# RTD_100R_INA_Comp.net
KiCad netlist of a schematic drawn in Altium Designer
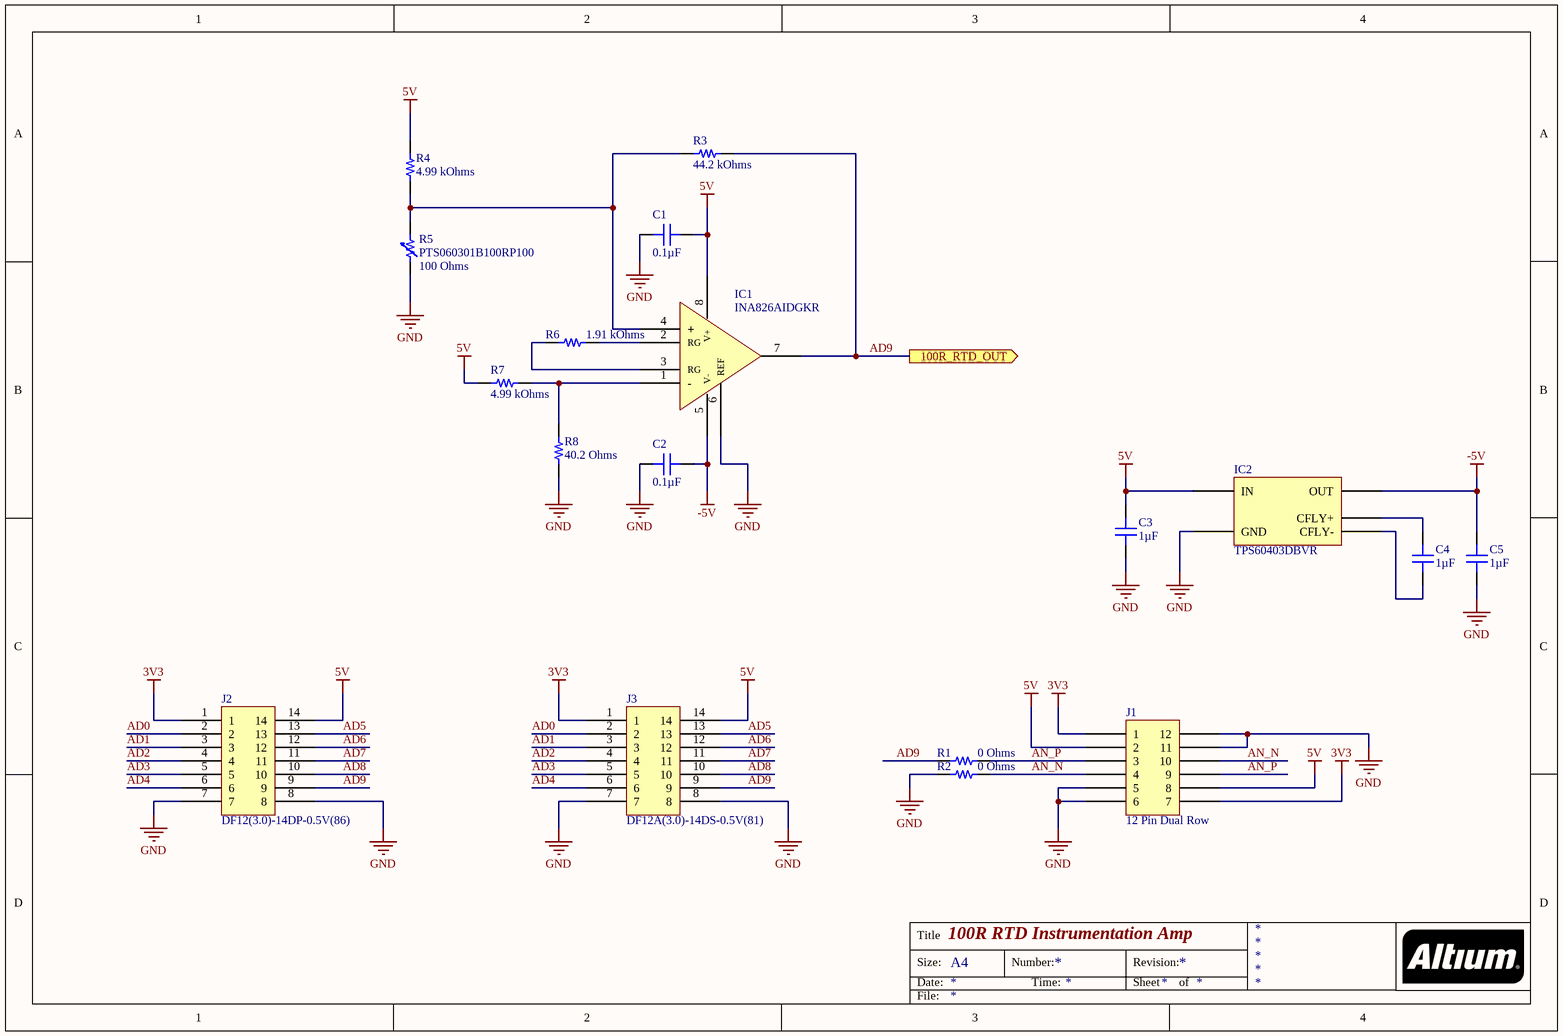
[diagram p0: RTD 100R INA Comp.SchDoc]

(export (version "E")
  (design (tool "Eeschema 10.0.6"))
  (components
    (comp (ref "C1")
      (value "0.1µF")
      (footprint "CAP 0603_1608")
      (description "CAP CER 0.1UF 16V Y5V 0603")
      (fields (field (name "PART NUMBER") "CC0603ZRY5V7BB104") (field (name "MANUFACTURER") "Yageo"))
      (libsource (lib "altiumlibrary.com") (part "Capacitor"))
    )
    (comp (ref "C2")
      (value "0.1µF")
      (footprint "CAP 0603_1608")
      (description "CAP CER 0.1UF 16V Y5V 0603")
      (fields (field (name "PART NUMBER") "CC0603ZRY5V7BB104") (field (name "MANUFACTURER") "Yageo"))
      (libsource (lib "altiumlibrary.com") (part "Capacitor"))
    )
    (comp (ref "C3")
      (value "1µF")
      (footprint "CAP 0603_1608")
      (description "CAP CER 1UF 25V X7R 0603")
      (fields
        (field (name "PART NUMBER") "CL10B105KA8NNNC")
        (field (name "MANUFACTURER") "Samsung Electro-Mechanics")
      )
      (libsource (lib "altiumlibrary.com") (part "Capacitor"))
    )
    (comp (ref "C4")
      (value "1µF")
      (footprint "CAP 0603_1608")
      (description "CAP CER 1UF 25V X7R 0603")
      (fields
        (field (name "PART NUMBER") "CL10B105KA8NNNC")
        (field (name "MANUFACTURER") "Samsung Electro-Mechanics")
      )
      (libsource (lib "altiumlibrary.com") (part "Capacitor"))
    )
    (comp (ref "C5")
      (value "1µF")
      (footprint "CAP 0603_1608")
      (description "CAP CER 1UF 25V X7R 0603")
      (fields
        (field (name "PART NUMBER") "CL10B105KA8NNNC")
        (field (name "MANUFACTURER") "Samsung Electro-Mechanics")
      )
      (libsource (lib "altiumlibrary.com") (part "Capacitor"))
    )
    (comp (ref "IC1")
      (value "INA826AIDGKR")
      (footprint "TI VSSOP-8 DGK")
      (description "IC INST AMP 1 CIRCUIT 8VSSOP")
      (fields (field (name "MANUFACTURER") "Texas Instruments"))
      (libsource (lib "altiumlibrary.com") (part "TI INA826"))
    )
    (comp (ref "IC2")
      (value "TPS60403DBVR")
      (footprint "TI SOT-23-5 DBV")
      (description "IC REG CHARG PUMP INV 60MA SOT23")
      (fields (field (name "MANUFACTURER") "Texas Instruments"))
      (libsource (lib "altiumlibrary.com") (part "TI TPS60403"))
    )
    (comp (ref "J1")
      (value "12 Pin Dual Row")
      (footprint "TE 5650118-3 Card Edge")
      (libsource (lib "CelestialUseful") (part "12 Pin Dual Row"))
    )
    (comp (ref "J2")
      (value "DF12(3.0)-14DP-0.5V(86)")
      (footprint "HIROSE DF12 3.0-14DP-0.5V 86")
      (description "CONN HDR 14POS SMD GOLD")
      (fields (field (name "MANUFACTURER") "Hirose Electric Co Ltd"))
      (libsource (lib "altiumlibrary.com") (part "14 Pin Dual Row"))
    )
    (comp (ref "J3")
      (value "DF12A(3.0)-14DS-0.5V(81)")
      (footprint "HIROSE DF12A 3.0-14DS-0.5V 81")
      (description "CONN RCPT 14POS SMD GOLD")
      (fields (field (name "MANUFACTURER") "Hirose Electric Co Ltd"))
      (libsource (lib "altiumlibrary.com") (part "14 Pin Dual Row"))
    )
    (comp (ref "R1")
      (value "0 Ohms")
      (footprint "RES 0603_1608")
      (description "RES SMD 0 OHM JUMPER 1/10W 0603")
      (fields
        (field (name "PART NUMBER") "ERJ-3GEY0R00V")
        (field (name "MANUFACTURER") "Panasonic Electronic Components")
      )
      (libsource (lib "altiumlibrary.com") (part "Resistor"))
    )
    (comp (ref "R2")
      (value "0 Ohms")
      (footprint "RES 0603_1608")
      (description "RES SMD 0 OHM JUMPER 1/10W 0603")
      (fields
        (field (name "PART NUMBER") "ERJ-3GEY0R00V")
        (field (name "MANUFACTURER") "Panasonic Electronic Components")
      )
      (libsource (lib "altiumlibrary.com") (part "Resistor"))
    )
    (comp (ref "R3")
      (value "44.2 kOhms")
      (footprint "RES 0603_1608")
      (description "RES SMD 44.2K OHM 1% 1/10W 0603")
      (fields
        (field (name "PART NUMBER") "ERJ-3EKF4422V")
        (field (name "MANUFACTURER") "Panasonic Electronic Components")
      )
      (libsource (lib "altiumlibrary.com") (part "Resistor"))
    )
    (comp (ref "R4")
      (value "4.99 kOhms")
      (footprint "RES 0603_1608")
      (description "RES SMD 4.99K OHM 1% 1/10W 0603")
      (fields
        (field (name "PART NUMBER") "ERJ-3EKF4991V")
        (field (name "MANUFACTURER") "Panasonic Electronic Components")
      )
      (libsource (lib "altiumlibrary.com") (part "Resistor"))
    )
    (comp (ref "R5")
      (value "PTS060301B100RP100")
      (footprint "RTD 0603_1608")
      (description "SENSOR RTD 100OHM 1% 0603")
      (fields (field (name "MANUFACTURER") "Vishay Beyschlag") (field (name "RESISTANCE @ 0°C") "100 Ohms"))
      (libsource (lib "altiumlibrary.com") (part "RTD"))
    )
    (comp (ref "R6")
      (value "1.91 kOhms")
      (footprint "RES 0603_1608")
      (description "RES SMD 1.91K OHM 1% 1/10W 0603")
      (fields
        (field (name "PART NUMBER") "ERJ-3EKF1911V")
        (field (name "MANUFACTURER") "Panasonic Electronic Components")
      )
      (libsource (lib "altiumlibrary.com") (part "Resistor"))
    )
    (comp (ref "R7")
      (value "4.99 kOhms")
      (footprint "RES 0603_1608")
      (description "RES SMD 4.99K OHM 1% 1/10W 0603")
      (fields
        (field (name "PART NUMBER") "ERJ-3EKF4991V")
        (field (name "MANUFACTURER") "Panasonic Electronic Components")
      )
      (libsource (lib "altiumlibrary.com") (part "Resistor"))
    )
    (comp (ref "R8")
      (value "40.2 Ohms")
      (footprint "RES 0603_1608")
      (description "RES SMD 40.2 OHM 1% 1/10W 0603")
      (fields
        (field (name "PART NUMBER") "ERJ-3EKF40R2V")
        (field (name "MANUFACTURER") "Panasonic Electronic Components")
      )
      (libsource (lib "altiumlibrary.com") (part "Resistor"))
    )
  )
  (nets
    (net (code "1") (name "-5V") (class "Default")
      (node (ref "C2") (pin "2") (pinfunction "2_2") (pintype "passive"))
      (node (ref "C5") (pin "2") (pinfunction "2_2") (pintype "passive"))
      (node (ref "IC1") (pin "5") (pinfunction "V-_5") (pintype "passive"))
      (node (ref "IC2") (pin "1") (pinfunction "OUT_1") (pintype "passive"))
    )
    (net (code "2") (name "/AD0") (class "Default")
      (node (ref "J2") (pin "2") (pinfunction "2_2") (pintype "passive"))
      (node (ref "J3") (pin "2") (pinfunction "2_2") (pintype "passive"))
    )
    (net (code "3") (name "/AD1") (class "Default")
      (node (ref "J2") (pin "3") (pinfunction "3_3") (pintype "passive"))
      (node (ref "J3") (pin "3") (pinfunction "3_3") (pintype "passive"))
    )
    (net (code "4") (name "/AD2") (class "Default")
      (node (ref "J2") (pin "4") (pinfunction "4_4") (pintype "passive"))
      (node (ref "J3") (pin "4") (pinfunction "4_4") (pintype "passive"))
    )
    (net (code "5") (name "/AD3") (class "Default")
      (node (ref "J2") (pin "5") (pinfunction "5_5") (pintype "passive"))
      (node (ref "J3") (pin "5") (pinfunction "5_5") (pintype "passive"))
    )
    (net (code "6") (name "/AD4") (class "Default")
      (node (ref "J2") (pin "6") (pinfunction "6_6") (pintype "passive"))
      (node (ref "J3") (pin "6") (pinfunction "6_6") (pintype "passive"))
    )
    (net (code "7") (name "/AD5") (class "Default")
      (node (ref "J2") (pin "13") (pinfunction "13_13") (pintype "passive"))
      (node (ref "J3") (pin "13") (pinfunction "13_13") (pintype "passive"))
    )
    (net (code "8") (name "/AD6") (class "Default")
      (node (ref "J2") (pin "12") (pinfunction "12_12") (pintype "passive"))
      (node (ref "J3") (pin "12") (pinfunction "12_12") (pintype "passive"))
    )
    (net (code "9") (name "/AD7") (class "Default")
      (node (ref "J2") (pin "11") (pinfunction "11_11") (pintype "passive"))
      (node (ref "J3") (pin "11") (pinfunction "11_11") (pintype "passive"))
    )
    (net (code "10") (name "/AD8") (class "Default")
      (node (ref "J2") (pin "10") (pinfunction "10_10") (pintype "passive"))
      (node (ref "J3") (pin "10") (pinfunction "10_10") (pintype "passive"))
    )
    (net (code "11") (name "/AD9") (class "Default")
      (node (ref "IC1") (pin "7") (pinfunction "OUT_7") (pintype "passive"))
      (node (ref "J2") (pin "9") (pinfunction "9_9") (pintype "passive"))
      (node (ref "J3") (pin "9") (pinfunction "9_9") (pintype "passive"))
      (node (ref "R1") (pin "1") (pinfunction "1_1") (pintype "passive"))
      (node (ref "R3") (pin "2") (pinfunction "2_2") (pintype "passive"))
    )
    (net (code "12") (name "/AN_N") (class "Default")
      (node (ref "J1") (pin "10") (pinfunction "10_10") (pintype "passive"))
      (node (ref "J1") (pin "4") (pinfunction "4_4") (pintype "passive"))
      (node (ref "R2") (pin "2") (pinfunction "2_2") (pintype "passive"))
    )
    (net (code "13") (name "/AN_P") (class "Default")
      (node (ref "J1") (pin "3") (pinfunction "3_3") (pintype "passive"))
      (node (ref "J1") (pin "9") (pinfunction "9_9") (pintype "passive"))
      (node (ref "R1") (pin "2") (pinfunction "2_2") (pintype "passive"))
    )
    (net (code "14") (name "3V3") (class "Default")
      (node (ref "J1") (pin "1") (pinfunction "1_1") (pintype "passive"))
      (node (ref "J1") (pin "7") (pinfunction "7_7") (pintype "passive"))
      (node (ref "J2") (pin "1") (pinfunction "1_1") (pintype "passive"))
      (node (ref "J3") (pin "1") (pinfunction "1_1") (pintype "passive"))
    )
    (net (code "15") (name "5V") (class "Default")
      (node (ref "C1") (pin "2") (pinfunction "2_2") (pintype "passive"))
      (node (ref "C3") (pin "2") (pinfunction "2_2") (pintype "passive"))
      (node (ref "IC1") (pin "8") (pinfunction "V+_8") (pintype "passive"))
      (node (ref "IC2") (pin "2") (pinfunction "IN_2") (pintype "passive"))
      (node (ref "J1") (pin "2") (pinfunction "2_2") (pintype "passive"))
      (node (ref "J1") (pin "8") (pinfunction "8_8") (pintype "passive"))
      (node (ref "J2") (pin "14") (pinfunction "14_14") (pintype "passive"))
      (node (ref "J3") (pin "14") (pinfunction "14_14") (pintype "passive"))
      (node (ref "R4") (pin "2") (pinfunction "2_2") (pintype "passive"))
      (node (ref "R7") (pin "2") (pinfunction "2_2") (pintype "passive"))
    )
    (net (code "16") (name "GND") (class "Default")
      (node (ref "C1") (pin "1") (pinfunction "1_1") (pintype "passive"))
      (node (ref "C2") (pin "1") (pinfunction "1_1") (pintype "passive"))
      (node (ref "C3") (pin "1") (pinfunction "1_1") (pintype "passive"))
      (node (ref "C5") (pin "1") (pinfunction "1_1") (pintype "passive"))
      (node (ref "IC1") (pin "6") (pinfunction "REF_6") (pintype "passive"))
      (node (ref "IC2") (pin "4") (pinfunction "GND_4") (pintype "passive"))
      (node (ref "J1") (pin "11") (pinfunction "11_11") (pintype "passive"))
      (node (ref "J1") (pin "12") (pinfunction "12_12") (pintype "passive"))
      (node (ref "J1") (pin "5") (pinfunction "5_5") (pintype "passive"))
      (node (ref "J1") (pin "6") (pinfunction "6_6") (pintype "passive"))
      (node (ref "J2") (pin "7") (pinfunction "7_7") (pintype "passive"))
      (node (ref "J2") (pin "8") (pinfunction "8_8") (pintype "passive"))
      (node (ref "J3") (pin "7") (pinfunction "7_7") (pintype "passive"))
      (node (ref "J3") (pin "8") (pinfunction "8_8") (pintype "passive"))
      (node (ref "R2") (pin "1") (pinfunction "1_1") (pintype "passive"))
      (node (ref "R5") (pin "1") (pinfunction "1_1") (pintype "passive"))
      (node (ref "R8") (pin "1") (pinfunction "1_1") (pintype "passive"))
    )
    (net (code "17") (name "Net-(IC1-+)") (class "Default")
      (node (ref "IC1") (pin "4") (pinfunction "+_4") (pintype "passive"))
      (node (ref "R3") (pin "1") (pinfunction "1_1") (pintype "passive"))
      (node (ref "R4") (pin "1") (pinfunction "1_1") (pintype "passive"))
      (node (ref "R5") (pin "2") (pinfunction "2_2") (pintype "passive"))
    )
    (net (code "18") (name "Net-(IC1--)") (class "Default")
      (node (ref "IC1") (pin "1") (pinfunction "-_1") (pintype "passive"))
      (node (ref "R7") (pin "1") (pinfunction "1_1") (pintype "passive"))
      (node (ref "R8") (pin "2") (pinfunction "2_2") (pintype "passive"))
    )
    (net (code "19") (name "Net-(IC1-RG-Pad2)") (class "Default")
      (node (ref "IC1") (pin "2") (pinfunction "RG_2") (pintype "passive"))
      (node (ref "R6") (pin "1") (pinfunction "1_1") (pintype "passive"))
    )
    (net (code "20") (name "Net-(IC1-RG-Pad3)") (class "Default")
      (node (ref "IC1") (pin "3") (pinfunction "RG_3") (pintype "passive"))
      (node (ref "R6") (pin "2") (pinfunction "2_2") (pintype "passive"))
    )
    (net (code "21") (name "Net-(IC2-CFLY+)") (class "Default")
      (node (ref "C4") (pin "2") (pinfunction "2_2") (pintype "passive"))
      (node (ref "IC2") (pin "5") (pinfunction "CFLY+_5") (pintype "passive"))
    )
    (net (code "22") (name "Net-(IC2-CFLY-)") (class "Default")
      (node (ref "C4") (pin "1") (pinfunction "1_1") (pintype "passive"))
      (node (ref "IC2") (pin "3") (pinfunction "CFLY-_3") (pintype "passive"))
    )
  )
)
